# Battery_Monitoring.net
KiCad netlist of a schematic drawn in Altium Designer
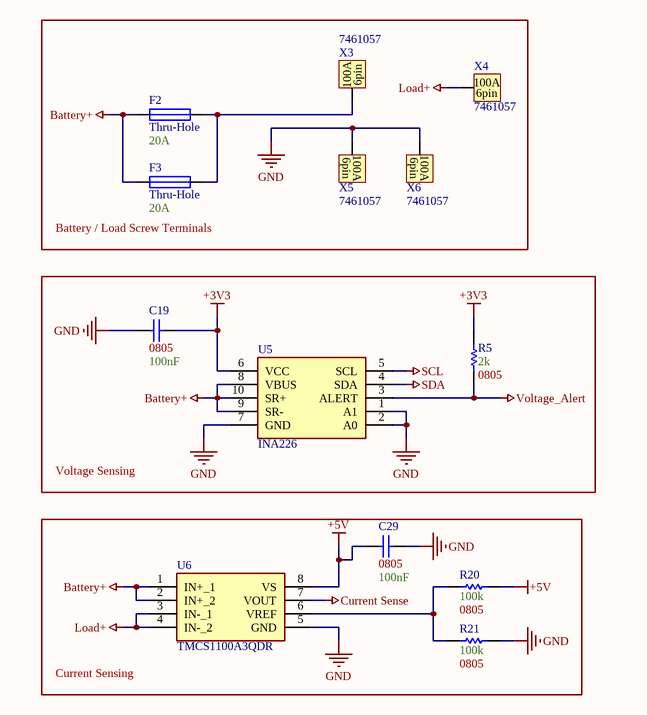
[diagram p0: Battery Monitoring.SchDoc]

(export (version "E")
  (design (tool "Eeschema 10.0.6"))
  (components
    (comp (ref "C19")
      (value "[Cap] SMD Nonpolarized")
      (footprint "[Cap] SMD 0805")
      (fields (field (name "SIZE PACKAGE") "0805") (field (name "CAPACITANCE") "100nF"))
      (libsource (lib "RADM Components") (part "[Cap] SMD Nonpolarized"))
    )
    (comp (ref "C29")
      (value "[Cap] SMD Nonpolarized")
      (footprint "[Cap] SMD 0805")
      (fields (field (name "SIZE PACKAGE") "0805") (field (name "CAPACITANCE") "100nF"))
      (libsource (lib "RADM Components") (part "[Cap] SMD Nonpolarized"))
    )
    (comp (ref "F2")
      (value "Thru-Hole")
      (footprint "[Fuse] Blade (2)")
      (fields (field (name "CAPACITY") "20A"))
      (libsource (lib "RADM Components") (part "[Fuse] Thru-Hole Blade"))
    )
    (comp (ref "F3")
      (value "Thru-Hole")
      (footprint "[Fuse] Blade (2)")
      (fields (field (name "CAPACITY") "20A"))
      (libsource (lib "RADM Components") (part "[Fuse] Thru-Hole Blade"))
    )
    (comp (ref "R5")
      (value "[Res] SMD Resistor")
      (footprint "[Res] SMD 0805")
      (fields (field (name "RESISTANCE") "2k") (field (name "SIZE PACKAGE") "0805"))
      (libsource (lib "RADM Components") (part "[Res] SMD Resistor"))
    )
    (comp (ref "R20")
      (value "[Res] SMD Resistor")
      (footprint "[Res] SMD 0805")
      (fields (field (name "RESISTANCE") "100k") (field (name "SIZE PACKAGE") "0805"))
      (libsource (lib "RADM Components") (part "[Res] SMD Resistor"))
    )
    (comp (ref "R21")
      (value "[Res] SMD Resistor")
      (footprint "[Res] SMD 0805")
      (fields (field (name "RESISTANCE") "100k") (field (name "SIZE PACKAGE") "0805"))
      (libsource (lib "RADM Components") (part "[Res] SMD Resistor"))
    )
    (comp (ref "U5")
      (value "INA226")
      (footprint "[IC] Battery Voltage Monitor (36V)")
      (description "INA226AIDGST")
      (libsource (lib "RADM Components") (part "[IC] Battery Voltage Monitor (36V)"))
    )
    (comp (ref "U6")
      (value "TMCS1100A3QDR")
      (footprint "[IC] Hall Effect Current Sensor")
      (description "TMCS1100")
      (libsource (lib "RADM Components") (part "[IC] Hall Effect Current Sensor"))
    )
    (comp (ref "X3")
      (value "7461057")
      (footprint "[Port] Shank Connector (100A)")
      (description "7461057, internal thread")
      (libsource (lib "") (part "[Port] Shank Connector (100A)_2"))
    )
    (comp (ref "X4")
      (value "7461057")
      (footprint "[Port] Shank Connector (100A)")
      (description "7461057, internal thread")
      (libsource (lib "") (part "[Port] Shank Connector (100A)_1"))
    )
    (comp (ref "X5")
      (value "7461057")
      (footprint "[Port] Shank Connector (100A)")
      (description "7461057, internal thread")
      (libsource (lib "RADM Components") (part "[Port] Shank Connector (100A)"))
    )
    (comp (ref "X6")
      (value "7461057")
      (footprint "[Port] Shank Connector (100A)")
      (description "7461057, internal thread")
      (libsource (lib "RADM Components") (part "[Port] Shank Connector (100A)"))
    )
  )
  (nets
    (net (code "1") (name "+3V3") (class "Default")
      (node (ref "C19") (pin "1") (pinfunction "1_1") (pintype "passive"))
      (node (ref "R5") (pin "2") (pinfunction "2_2") (pintype "passive"))
      (node (ref "U5") (pin "6") (pinfunction "VCC_6") (pintype "passive"))
    )
    (net (code "2") (name "+5V") (class "Default")
      (node (ref "C29") (pin "2") (pinfunction "2_2") (pintype "passive"))
      (node (ref "R20") (pin "2") (pinfunction "2_2") (pintype "passive"))
      (node (ref "U6") (pin "8") (pinfunction "VS_8") (pintype "passive"))
    )
    (net (code "3") (name "Battery+") (class "Default")
      (node (ref "F2") (pin "1") (pinfunction "1_1") (pintype "passive"))
      (node (ref "F3") (pin "1") (pinfunction "1_1") (pintype "passive"))
      (node (ref "U5") (pin "10") (pinfunction "SR+_10") (pintype "passive"))
      (node (ref "U5") (pin "8") (pinfunction "VBUS_8") (pintype "passive"))
      (node (ref "U5") (pin "9") (pinfunction "SR-_9") (pintype "passive"))
      (node (ref "U6") (pin "1") (pinfunction "IN+_1_1") (pintype "passive"))
      (node (ref "U6") (pin "2") (pinfunction "IN+_2_2") (pintype "passive"))
    )
    (net (code "4") (name "Current Sense") (class "Default")
      (node (ref "U6") (pin "7") (pinfunction "VOUT_7") (pintype "passive"))
    )
    (net (code "5") (name "GND") (class "Default")
      (node (ref "C19") (pin "2") (pinfunction "2_2") (pintype "passive"))
      (node (ref "C29") (pin "1") (pinfunction "1_1") (pintype "passive"))
      (node (ref "R21") (pin "1") (pinfunction "1_1") (pintype "passive"))
      (node (ref "U5") (pin "1") (pinfunction "A1_1") (pintype "passive"))
      (node (ref "U5") (pin "2") (pinfunction "A0_2") (pintype "passive"))
      (node (ref "U5") (pin "7") (pinfunction "GND_7") (pintype "passive"))
      (node (ref "U6") (pin "5") (pinfunction "GND_5") (pintype "passive"))
      (node (ref "X5") (pin "1") (pinfunction "4_1") (pintype "power_in"))
      (node (ref "X6") (pin "1") (pinfunction "4_1") (pintype "power_in"))
    )
    (net (code "6") (name "Load+") (class "Default")
      (node (ref "U6") (pin "3") (pinfunction "IN-_1_3") (pintype "passive"))
      (node (ref "U6") (pin "4") (pinfunction "IN-_2_4") (pintype "passive"))
      (node (ref "X4") (pin "1") (pinfunction "4_1") (pintype "power_in"))
    )
    (net (code "7") (name "Net-(U6-VREF)") (class "Default")
      (node (ref "R20") (pin "1") (pinfunction "1_1") (pintype "passive"))
      (node (ref "R21") (pin "2") (pinfunction "2_2") (pintype "passive"))
      (node (ref "U6") (pin "6") (pinfunction "VREF_6") (pintype "passive"))
    )
    (net (code "8") (name "Net-(X3-4)") (class "Default")
      (node (ref "F2") (pin "2") (pinfunction "2_2") (pintype "passive"))
      (node (ref "F3") (pin "2") (pinfunction "2_2") (pintype "passive"))
      (node (ref "X3") (pin "1") (pinfunction "4_1") (pintype "power_in"))
    )
    (net (code "9") (name "SCL") (class "Default")
      (node (ref "U5") (pin "5") (pinfunction "SCL_5") (pintype "passive"))
    )
    (net (code "10") (name "SDA") (class "Default")
      (node (ref "U5") (pin "4") (pinfunction "SDA_4") (pintype "passive"))
    )
    (net (code "11") (name "Voltage_Alert") (class "Default")
      (node (ref "R5") (pin "1") (pinfunction "1_1") (pintype "passive"))
      (node (ref "U5") (pin "3") (pinfunction "ALERT_3") (pintype "passive"))
    )
  )
)
